# POS5V.net
KiCad netlist of a schematic drawn in Altium Designer
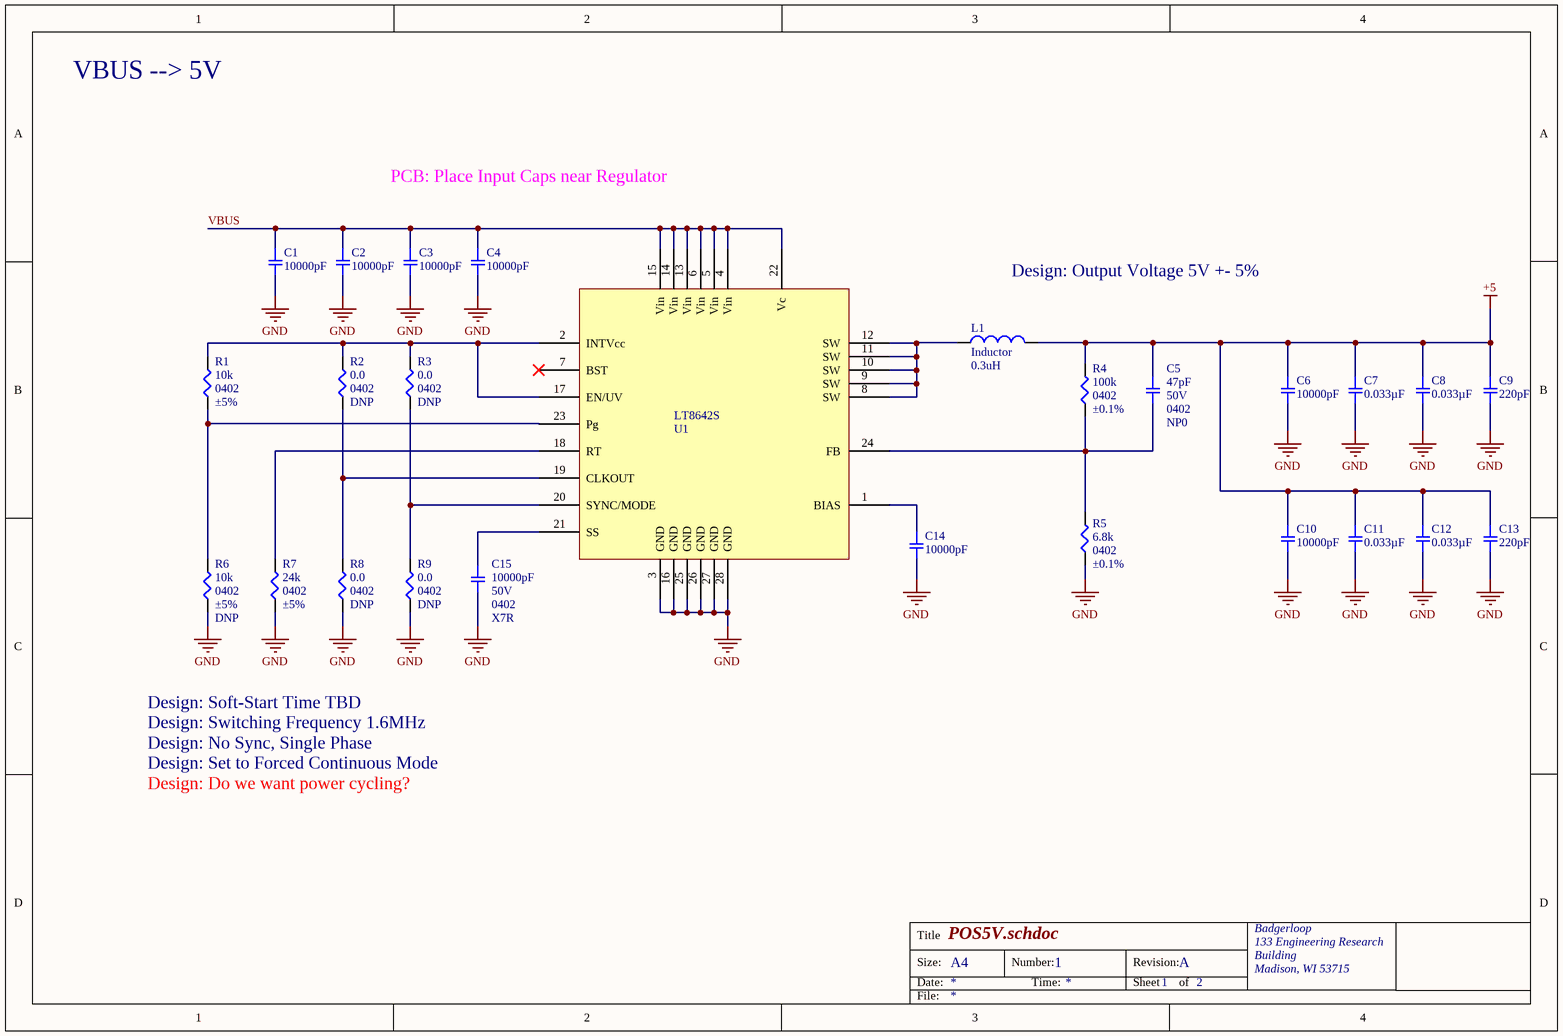
[diagram p0: POS5V.schdoc]

(export (version "E")
  (design (tool "Eeschema 10.0.6"))
  (components
    (comp (ref "C1")
      (value "10000pF")
      (footprint "SMD-0805C")
      (description "CAP CER 10000PF 250V X7T 0805")
      (fields
        (field (name "DIGI-KEY PART NUMBER") "490-13986-1-ND")
        (field (name "PART NUMBER") "GC321AD72E103KX01D")
      )
      (libsource (lib "capacitor") (part "GC321AD72E103KX01D"))
    )
    (comp (ref "C2")
      (value "10000pF")
      (footprint "SMD-0805C")
      (description "CAP CER 10000PF 250V X7T 0805")
      (fields
        (field (name "DIGI-KEY PART NUMBER") "490-13986-1-ND")
        (field (name "PART NUMBER") "GC321AD72E103KX01D")
      )
      (libsource (lib "capacitor") (part "GC321AD72E103KX01D"))
    )
    (comp (ref "C3")
      (value "10000pF")
      (footprint "SMD-0805C")
      (description "CAP CER 10000PF 250V X7T 0805")
      (fields
        (field (name "DIGI-KEY PART NUMBER") "490-13986-1-ND")
        (field (name "PART NUMBER") "GC321AD72E103KX01D")
      )
      (libsource (lib "capacitor") (part "GC321AD72E103KX01D"))
    )
    (comp (ref "C4")
      (value "10000pF")
      (footprint "SMD-0805C")
      (description "CAP CER 10000PF 250V X7T 0805")
      (fields
        (field (name "DIGI-KEY PART NUMBER") "490-13986-1-ND")
        (field (name "PART NUMBER") "GC321AD72E103KX01D")
      )
      (libsource (lib "capacitor") (part "GC321AD72E103KX01D"))
    )
    (comp (ref "C5")
      (value "47pF")
      (footprint "SMD-0402C")
      (description "CAP CER 47PF 50V NP0 0402")
      (fields
        (field (name "DIGI-KEY PART NUMBER") "490-10670-1-ND")
        (field (name "PART NUMBER") "GCM1555C1H470JA16D")
        (field (name "VOLTAGE") "50V")
        (field (name "TEMPERATURE COEFFICIENT") "NP0")
        (field (name "PACKAGE / CASE") "0402")
      )
      (libsource (lib "capacitor") (part "GCM1555C1H470JA16D"))
    )
    (comp (ref "C6")
      (value "10000pF")
      (footprint "SMD-0805C")
      (description "CAP CER 10000PF 250V X7T 0805")
      (fields
        (field (name "DIGI-KEY PART NUMBER") "490-13986-1-ND")
        (field (name "PART NUMBER") "GC321AD72E103KX01D")
      )
      (libsource (lib "capacitor") (part "GC321AD72E103KX01D"))
    )
    (comp (ref "C7")
      (value "0.033µF")
      (footprint "SMD-1206C")
      (description "CAP CER 0.033UF 250V X7T 1206")
      (fields
        (field (name "DIGI-KEY PART NUMBER") "490-13989-1-ND")
        (field (name "PART NUMBER") "GC331AD72E333KX01D")
      )
      (libsource (lib "capacitor") (part "GC331AD72E333KX01D"))
    )
    (comp (ref "C8")
      (value "0.033µF")
      (footprint "SMD-1206C")
      (description "CAP CER 0.033UF 250V X7T 1206")
      (fields
        (field (name "DIGI-KEY PART NUMBER") "490-13989-1-ND")
        (field (name "PART NUMBER") "GC331AD72E333KX01D")
      )
      (libsource (lib "capacitor") (part "GC331AD72E333KX01D"))
    )
    (comp (ref "C9")
      (value "220pF")
      (footprint "SMD-0402C")
      (description "CAP CER 220PF 50V NP0 0402")
      (fields
        (field (name "DIGI-KEY PART NUMBER") "490-4927-1-ND")
        (field (name "PART NUMBER") "GCM1555C1H221JA16D")
      )
      (libsource (lib "capacitor") (part "GCM1555C1H221JA16D"))
    )
    (comp (ref "C10")
      (value "10000pF")
      (footprint "SMD-0805C")
      (description "CAP CER 10000PF 250V X7T 0805")
      (fields
        (field (name "DIGI-KEY PART NUMBER") "490-13986-1-ND")
        (field (name "PART NUMBER") "GC321AD72E103KX01D")
      )
      (libsource (lib "capacitor") (part "GC321AD72E103KX01D"))
    )
    (comp (ref "C11")
      (value "0.033µF")
      (footprint "SMD-1206C")
      (description "CAP CER 0.033UF 250V X7T 1206")
      (fields
        (field (name "DIGI-KEY PART NUMBER") "490-13989-1-ND")
        (field (name "PART NUMBER") "GC331AD72E333KX01D")
      )
      (libsource (lib "capacitor") (part "GC331AD72E333KX01D"))
    )
    (comp (ref "C12")
      (value "0.033µF")
      (footprint "SMD-1206C")
      (description "CAP CER 0.033UF 250V X7T 1206")
      (fields
        (field (name "DIGI-KEY PART NUMBER") "490-13989-1-ND")
        (field (name "PART NUMBER") "GC331AD72E333KX01D")
      )
      (libsource (lib "capacitor") (part "GC331AD72E333KX01D"))
    )
    (comp (ref "C13")
      (value "220pF")
      (footprint "SMD-0402C")
      (description "CAP CER 220PF 50V NP0 0402")
      (fields
        (field (name "DIGI-KEY PART NUMBER") "490-4927-1-ND")
        (field (name "PART NUMBER") "GCM1555C1H221JA16D")
      )
      (libsource (lib "capacitor") (part "GCM1555C1H221JA16D"))
    )
    (comp (ref "C14")
      (value "10000pF")
      (footprint "SMD-0805C")
      (description "CAP CER 10000PF 250V X7T 0805")
      (fields
        (field (name "DIGI-KEY PART NUMBER") "490-13986-1-ND")
        (field (name "PART NUMBER") "GC321AD72E103KX01D")
      )
      (libsource (lib "capacitor") (part "GC321AD72E103KX01D"))
    )
    (comp (ref "C15")
      (value "10000pF")
      (footprint "SMD-0402C")
      (description "CAP CER 10000PF 50V X7R 0402")
      (fields
        (field (name "DIGI-KEY PART NUMBER") "490-4762-1-ND")
        (field (name "PART NUMBER") "GCM155R71H103KA55D")
        (field (name "VOLTAGE") "50V")
        (field (name "TEMPERATURE COEFFICIENT") "X7R")
        (field (name "PACKAGE / CASE") "0402")
      )
      (libsource (lib "capacitor") (part "GCM155R71H103KA55D"))
    )
    (comp (ref "L1")
      (value "Inductor")
      (footprint "0402-A")
      (fields (field (name "ALTIUM_VALUE") "0.3uH") (field (name "PUBLISHER") "Altium Limited"))
      (libsource (lib "Miscellaneous Devices") (part "Inductor"))
    )
    (comp (ref "R1")
      (value "10k")
      (footprint "SMD-0402-RES")
      (description "RES SMD 10K OHM 5% 1/10W 0402")
      (fields
        (field (name "PART NUMBER") "ERJ-2GEJ103X")
        (field (name "DIGI-KEY PART NUMBER") "P10KJCT-ND")
        (field (name "TOLERANCE") "±5%")
        (field (name "SUPPLIER DEVICE PACKAGE") "0402")
      )
      (libsource (lib "resistor") (part "ERJ-2GEJ103X"))
    )
    (comp (ref "R2")
      (value "0.0")
      (footprint "SMD-0402-RES")
      (description "RES SMD 0.0OHM JUMPER 1/10W 0402")
      (fields
        (field (name "PART NUMBER") "ERJ-2GE0R00X")
        (field (name "DIGI-KEY PART NUMBER") "P0.0JCT-ND")
        (field (name "SUPPLIER DEVICE PACKAGE") "0402")
        (field (name "BOM") "DNP")
      )
      (libsource (lib "resistor") (part "ERJ-2GE0R00X"))
    )
    (comp (ref "R3")
      (value "0.0")
      (footprint "SMD-0402-RES")
      (description "RES SMD 0.0OHM JUMPER 1/10W 0402")
      (fields
        (field (name "PART NUMBER") "ERJ-2GE0R00X")
        (field (name "DIGI-KEY PART NUMBER") "P0.0JCT-ND")
        (field (name "SUPPLIER DEVICE PACKAGE") "0402")
        (field (name "BOM") "DNP")
      )
      (libsource (lib "resistor") (part "ERJ-2GE0R00X"))
    )
    (comp (ref "R4")
      (value "100k")
      (footprint "SMD-0402-RES")
      (description "RES SMD 100K OHM 5% 1/10W 0402")
      (fields
        (field (name "PART NUMBER") "ERJ-2GEJ104X")
        (field (name "DIGI-KEY PART NUMBER") "P100KJCT-ND")
        (field (name "TOLERANCE") "±0.1%")
        (field (name "SUPPLIER DEVICE PACKAGE") "0402")
      )
      (libsource (lib "resistor") (part "ERJ-2GEJ104X"))
    )
    (comp (ref "R5")
      (value "6.8k")
      (footprint "SMD-0402-RES")
      (description "RES SMD 6.8K OHM 5% 1/10W 0402")
      (fields
        (field (name "PART NUMBER") "ERJ-2GEJ682X")
        (field (name "DIGI-KEY PART NUMBER") "P6.8KJCT-ND")
        (field (name "TOLERANCE") "±0.1%")
        (field (name "SUPPLIER DEVICE PACKAGE") "0402")
      )
      (libsource (lib "resistor") (part "ERJ-2GEJ682X"))
    )
    (comp (ref "R6")
      (value "10k")
      (footprint "SMD-0402-RES")
      (description "RES SMD 10K OHM 5% 1/10W 0402")
      (fields
        (field (name "PART NUMBER") "ERJ-2GEJ103X")
        (field (name "DIGI-KEY PART NUMBER") "P10KJCT-ND")
        (field (name "TOLERANCE") "±5%")
        (field (name "SUPPLIER DEVICE PACKAGE") "0402")
        (field (name "BOM_CONFIG") "DNP")
      )
      (libsource (lib "resistor") (part "ERJ-2GEJ103X"))
    )
    (comp (ref "R7")
      (value "24k")
      (footprint "SMD-0402-RES")
      (description "RES SMD 24K OHM 5% 1/10W 0402")
      (fields
        (field (name "PART NUMBER") "ERJ-2GEJ243X")
        (field (name "DIGI-KEY PART NUMBER") "P24KJCT-ND")
        (field (name "TOLERANCE") "±5%")
        (field (name "SUPPLIER DEVICE PACKAGE") "0402")
      )
      (libsource (lib "resistor") (part "ERJ-2GEJ243X"))
    )
    (comp (ref "R8")
      (value "0.0")
      (footprint "SMD-0402-RES")
      (description "RES SMD 0.0OHM JUMPER 1/10W 0402")
      (fields
        (field (name "PART NUMBER") "ERJ-2GE0R00X")
        (field (name "DIGI-KEY PART NUMBER") "P0.0JCT-ND")
        (field (name "SUPPLIER DEVICE PACKAGE") "0402")
        (field (name "BOM") "DNP")
      )
      (libsource (lib "resistor") (part "ERJ-2GE0R00X"))
    )
    (comp (ref "R9")
      (value "0.0")
      (footprint "SMD-0402-RES")
      (description "RES SMD 0.0OHM JUMPER 1/10W 0402")
      (fields
        (field (name "PART NUMBER") "ERJ-2GE0R00X")
        (field (name "DIGI-KEY PART NUMBER") "P0.0JCT-ND")
        (field (name "SUPPLIER DEVICE PACKAGE") "0402")
        (field (name "BOM") "DNP")
      )
      (libsource (lib "resistor") (part "ERJ-2GE0R00X"))
    )
    (comp (ref "U1")
      (value "LT8642S")
      (description "18V, 10A Synchronous\r\nStep-Down Silent Switcher 2")
      (libsource (lib "ic") (part "LT8642S"))
    )
  )
  (nets
    (net (code "1") (name "+5") (class "Default")
      (node (ref "C10") (pin "1") (pinfunction "1_1") (pintype "passive"))
      (node (ref "C11") (pin "1") (pinfunction "1_1") (pintype "passive"))
      (node (ref "C12") (pin "1") (pinfunction "1_1") (pintype "passive"))
      (node (ref "C13") (pin "1") (pinfunction "1_1") (pintype "passive"))
      (node (ref "C5") (pin "1") (pinfunction "1_1") (pintype "passive"))
      (node (ref "C6") (pin "1") (pinfunction "1_1") (pintype "passive"))
      (node (ref "C7") (pin "1") (pinfunction "1_1") (pintype "passive"))
      (node (ref "C8") (pin "1") (pinfunction "1_1") (pintype "passive"))
      (node (ref "C9") (pin "1") (pinfunction "1_1") (pintype "passive"))
      (node (ref "L1") (pin "2") (pinfunction "2_2") (pintype "passive"))
      (node (ref "R4") (pin "2") (pinfunction "2_2") (pintype "passive"))
    )
    (net (code "2") (name "/VBUS") (class "Default")
      (node (ref "C1") (pin "1") (pinfunction "1_1") (pintype "passive"))
      (node (ref "C2") (pin "1") (pinfunction "1_1") (pintype "passive"))
      (node (ref "C3") (pin "1") (pinfunction "1_1") (pintype "passive"))
      (node (ref "C4") (pin "1") (pinfunction "1_1") (pintype "passive"))
      (node (ref "U1") (pin "13") (pinfunction "Vin_13") (pintype "power_in"))
      (node (ref "U1") (pin "14") (pinfunction "Vin_14") (pintype "power_in"))
      (node (ref "U1") (pin "15") (pinfunction "Vin_15") (pintype "power_in"))
      (node (ref "U1") (pin "22") (pinfunction "Vc_22") (pintype "passive"))
      (node (ref "U1") (pin "4") (pinfunction "Vin_4") (pintype "power_in"))
      (node (ref "U1") (pin "5") (pinfunction "Vin_5") (pintype "power_in"))
      (node (ref "U1") (pin "6") (pinfunction "Vin_6") (pintype "power_in"))
    )
    (net (code "3") (name "GND") (class "Default")
      (node (ref "C1") (pin "2") (pinfunction "2_2") (pintype "passive"))
      (node (ref "C10") (pin "2") (pinfunction "2_2") (pintype "passive"))
      (node (ref "C11") (pin "2") (pinfunction "2_2") (pintype "passive"))
      (node (ref "C12") (pin "2") (pinfunction "2_2") (pintype "passive"))
      (node (ref "C13") (pin "2") (pinfunction "2_2") (pintype "passive"))
      (node (ref "C14") (pin "2") (pinfunction "2_2") (pintype "passive"))
      (node (ref "C15") (pin "2") (pinfunction "2_2") (pintype "passive"))
      (node (ref "C2") (pin "2") (pinfunction "2_2") (pintype "passive"))
      (node (ref "C3") (pin "2") (pinfunction "2_2") (pintype "passive"))
      (node (ref "C4") (pin "2") (pinfunction "2_2") (pintype "passive"))
      (node (ref "C6") (pin "2") (pinfunction "2_2") (pintype "passive"))
      (node (ref "C7") (pin "2") (pinfunction "2_2") (pintype "passive"))
      (node (ref "C8") (pin "2") (pinfunction "2_2") (pintype "passive"))
      (node (ref "C9") (pin "2") (pinfunction "2_2") (pintype "passive"))
      (node (ref "R5") (pin "1") (pinfunction "1_1") (pintype "passive"))
      (node (ref "R6") (pin "1") (pinfunction "1_1") (pintype "passive"))
      (node (ref "R7") (pin "1") (pinfunction "1_1") (pintype "passive"))
      (node (ref "R8") (pin "1") (pinfunction "1_1") (pintype "passive"))
      (node (ref "R9") (pin "1") (pinfunction "1_1") (pintype "passive"))
      (node (ref "U1") (pin "16") (pinfunction "GND_16") (pintype "power_in"))
      (node (ref "U1") (pin "25") (pinfunction "GND_25") (pintype "power_in"))
      (node (ref "U1") (pin "26") (pinfunction "GND_26") (pintype "power_in"))
      (node (ref "U1") (pin "27") (pinfunction "GND_27") (pintype "power_in"))
      (node (ref "U1") (pin "28") (pinfunction "GND_28") (pintype "power_in"))
      (node (ref "U1") (pin "3") (pinfunction "GND_3") (pintype "power_in"))
    )
    (net (code "4") (name "Net-(L1-Pad1)") (class "Default")
      (node (ref "L1") (pin "1") (pinfunction "1_1") (pintype "passive"))
      (node (ref "U1") (pin "10") (pinfunction "SW_10") (pintype "passive"))
      (node (ref "U1") (pin "11") (pinfunction "SW_11") (pintype "passive"))
      (node (ref "U1") (pin "12") (pinfunction "SW_12") (pintype "passive"))
      (node (ref "U1") (pin "8") (pinfunction "SW_8") (pintype "passive"))
      (node (ref "U1") (pin "9") (pinfunction "SW_9") (pintype "passive"))
    )
    (net (code "5") (name "Net-(U1-BIAS)") (class "Default")
      (node (ref "C14") (pin "1") (pinfunction "1_1") (pintype "passive"))
      (node (ref "U1") (pin "1") (pinfunction "BIAS_1") (pintype "passive"))
    )
    (net (code "6") (name "Net-(U1-CLKOUT)") (class "Default")
      (node (ref "R2") (pin "1") (pinfunction "1_1") (pintype "passive"))
      (node (ref "R8") (pin "2") (pinfunction "2_2") (pintype "passive"))
      (node (ref "U1") (pin "19") (pinfunction "CLKOUT_19") (pintype "passive"))
    )
    (net (code "7") (name "Net-(U1-EN{slash}UV)") (class "Default")
      (node (ref "R1") (pin "2") (pinfunction "2_2") (pintype "passive"))
      (node (ref "R2") (pin "2") (pinfunction "2_2") (pintype "passive"))
      (node (ref "R3") (pin "2") (pinfunction "2_2") (pintype "passive"))
      (node (ref "U1") (pin "17") (pinfunction "EN/UV_17") (pintype "passive"))
      (node (ref "U1") (pin "2") (pinfunction "INTVcc_2") (pintype "passive"))
    )
    (net (code "8") (name "Net-(U1-FB)") (class "Default")
      (node (ref "C5") (pin "2") (pinfunction "2_2") (pintype "passive"))
      (node (ref "R4") (pin "1") (pinfunction "1_1") (pintype "passive"))
      (node (ref "R5") (pin "2") (pinfunction "2_2") (pintype "passive"))
      (node (ref "U1") (pin "24") (pinfunction "FB_24") (pintype "passive"))
    )
    (net (code "9") (name "Net-(U1-Pg)") (class "Default")
      (node (ref "R1") (pin "1") (pinfunction "1_1") (pintype "passive"))
      (node (ref "R6") (pin "2") (pinfunction "2_2") (pintype "passive"))
      (node (ref "U1") (pin "23") (pinfunction "Pg_23") (pintype "passive"))
    )
    (net (code "10") (name "Net-(U1-RT)") (class "Default")
      (node (ref "R7") (pin "2") (pinfunction "2_2") (pintype "passive"))
      (node (ref "U1") (pin "18") (pinfunction "RT_18") (pintype "passive"))
    )
    (net (code "11") (name "Net-(U1-SS)") (class "Default")
      (node (ref "C15") (pin "1") (pinfunction "1_1") (pintype "passive"))
      (node (ref "U1") (pin "21") (pinfunction "SS_21") (pintype "passive"))
    )
    (net (code "12") (name "Net-(U1-SYNC{slash}MODE)") (class "Default")
      (node (ref "R3") (pin "1") (pinfunction "1_1") (pintype "passive"))
      (node (ref "R9") (pin "2") (pinfunction "2_2") (pintype "passive"))
      (node (ref "U1") (pin "20") (pinfunction "SYNC/MODE_20") (pintype "passive"))
    )
    (net (code "13") (name "unconnected-(U1-BST-Pad7)") (class "Default")
      (node (ref "U1") (pin "7") (pinfunction "BST_7") (pintype "passive+no_connect"))
    )
  )
)
